# rfidboard.net
KiCad netlist of a schematic drawn in EAGLE
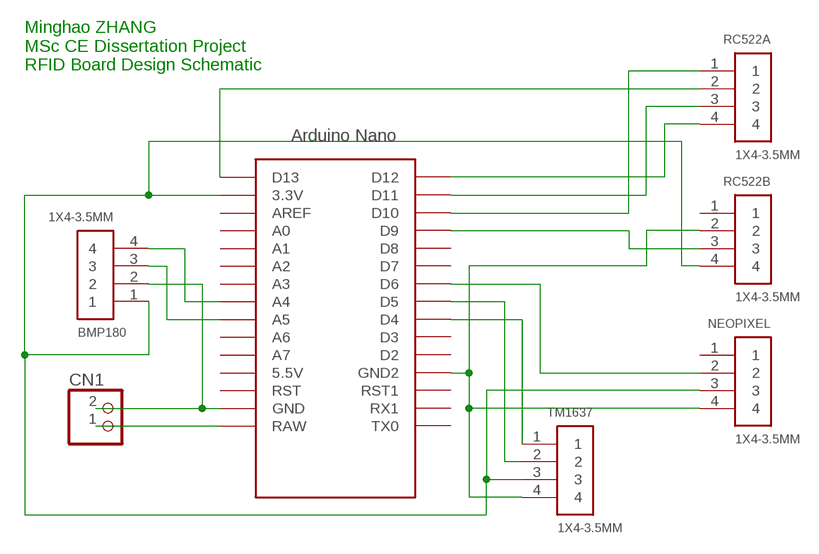
[diagram p0: schematic, sheet 1]

(export (version "E")
  (design (tool "Eeschema 10.0.6"))
  (components
    (comp (ref "BMP180")
      (value "1X4-3.5MM")
      (footprint "eagle-import:1X04-3.5MM")
      (libsource (lib "eagle-import") (part "1X4-3.5MM"))
    )
    (comp (ref "CN1")
      (value "JST_2PIN-SMT")
      (footprint "eagle-import:JST-PH-2-SMT")
      (libsource (lib "eagle-import") (part "JST_2PIN-SMT"))
    )
    (comp (ref "NEOPIXEL")
      (value "1X4-3.5MM")
      (footprint "eagle-import:1X04-3.5MM")
      (libsource (lib "eagle-import") (part "1X4-3.5MM"))
    )
    (comp (ref "RC522A")
      (value "1X4-3.5MM")
      (footprint "eagle-import:1X04-3.5MM")
      (libsource (lib "eagle-import") (part "1X4-3.5MM"))
    )
    (comp (ref "RC522B")
      (value "1X4-3.5MM")
      (footprint "eagle-import:1X04-3.5MM")
      (libsource (lib "eagle-import") (part "1X4-3.5MM"))
    )
    (comp (ref "TM1637")
      (value "1X4-3.5MM")
      (footprint "eagle-import:1X04-3.5MM")
      (libsource (lib "eagle-import") (part "1X4-3.5MM"))
    )
    (comp (ref "U$1")
      (value "NANO")
      (footprint "eagle-import:NANO")
      (libsource (lib "eagle-import") (part "NANO"))
    )
  )
  (nets
    (net (code "1") (name "Net-(BMP180-Pad1)") (class "Default")
      (node (ref "BMP180") (pin "1") (pinfunction "1_1") (pintype "bidirectional"))
      (node (ref "NEOPIXEL") (pin "3") (pinfunction "3_3") (pintype "bidirectional"))
      (node (ref "RC522B") (pin "4") (pinfunction "4_4") (pintype "bidirectional"))
      (node (ref "TM1637") (pin "3") (pinfunction "3_3") (pintype "bidirectional"))
      (node (ref "U$1") (pin "3.3V") (pinfunction "3.3V_3.3V") (pintype "bidirectional"))
    )
    (net (code "2") (name "Net-(BMP180-Pad3)") (class "Default")
      (node (ref "BMP180") (pin "3") (pinfunction "3_3") (pintype "bidirectional"))
      (node (ref "U$1") (pin "A5") (pinfunction "A5_A5") (pintype "bidirectional"))
    )
    (net (code "3") (name "Net-(BMP180-Pad4)") (class "Default")
      (node (ref "BMP180") (pin "4") (pinfunction "4_4") (pintype "bidirectional"))
      (node (ref "U$1") (pin "A4") (pinfunction "A4_A4") (pintype "bidirectional"))
    )
    (net (code "4") (name "Net-(CN1-1)") (class "Default")
      (node (ref "BMP180") (pin "2") (pinfunction "2_2") (pintype "bidirectional"))
      (node (ref "CN1") (pin "2") (pinfunction "1_2") (pintype "passive"))
      (node (ref "U$1") (pin "GND") (pinfunction "GND_GND") (pintype "bidirectional"))
    )
    (net (code "5") (name "Net-(CN1-2)") (class "Default")
      (node (ref "CN1") (pin "1") (pinfunction "2_1") (pintype "passive"))
      (node (ref "U$1") (pin "RAW") (pinfunction "RAW_RAW") (pintype "bidirectional"))
    )
    (net (code "6") (name "Net-(NEOPIXEL-Pad2)") (class "Default")
      (node (ref "NEOPIXEL") (pin "2") (pinfunction "2_2") (pintype "bidirectional"))
      (node (ref "U$1") (pin "D6") (pinfunction "D6_D6") (pintype "bidirectional"))
    )
    (net (code "7") (name "Net-(RC522A-Pad1)") (class "Default")
      (node (ref "RC522A") (pin "1") (pinfunction "1_1") (pintype "bidirectional"))
      (node (ref "U$1") (pin "D10") (pinfunction "D10_D10") (pintype "bidirectional"))
    )
    (net (code "8") (name "Net-(RC522A-Pad2)") (class "Default")
      (node (ref "RC522A") (pin "2") (pinfunction "2_2") (pintype "bidirectional"))
      (node (ref "U$1") (pin "D13") (pinfunction "D13_D13") (pintype "bidirectional"))
    )
    (net (code "9") (name "Net-(RC522A-Pad3)") (class "Default")
      (node (ref "RC522A") (pin "3") (pinfunction "3_3") (pintype "bidirectional"))
      (node (ref "U$1") (pin "D11") (pinfunction "D11_D11") (pintype "bidirectional"))
    )
    (net (code "10") (name "Net-(RC522A-Pad4)") (class "Default")
      (node (ref "RC522A") (pin "4") (pinfunction "4_4") (pintype "bidirectional"))
      (node (ref "U$1") (pin "D12") (pinfunction "D12_D12") (pintype "bidirectional"))
    )
    (net (code "11") (name "Net-(RC522B-Pad3)") (class "Default")
      (node (ref "RC522B") (pin "3") (pinfunction "3_3") (pintype "bidirectional"))
      (node (ref "U$1") (pin "D9") (pinfunction "D9_D9") (pintype "bidirectional"))
    )
    (net (code "12") (name "Net-(TM1637-Pad1)") (class "Default")
      (node (ref "TM1637") (pin "1") (pinfunction "1_1") (pintype "bidirectional"))
      (node (ref "U$1") (pin "D4") (pinfunction "D4_D4") (pintype "bidirectional"))
    )
    (net (code "13") (name "Net-(TM1637-Pad2)") (class "Default")
      (node (ref "TM1637") (pin "2") (pinfunction "2_2") (pintype "bidirectional"))
      (node (ref "U$1") (pin "D5") (pinfunction "D5_D5") (pintype "bidirectional"))
    )
    (net (code "14") (name "Net-(U$1-GND2)") (class "Default")
      (node (ref "NEOPIXEL") (pin "4") (pinfunction "4_4") (pintype "bidirectional"))
      (node (ref "RC522B") (pin "2") (pinfunction "2_2") (pintype "bidirectional"))
      (node (ref "TM1637") (pin "4") (pinfunction "4_4") (pintype "bidirectional"))
      (node (ref "U$1") (pin "GND1") (pinfunction "GND2_GND1") (pintype "bidirectional"))
    )
    (net (code "15") (name "unconnected-(NEOPIXEL-Pad1)") (class "Default")
      (node (ref "NEOPIXEL") (pin "1") (pinfunction "1_1") (pintype "bidirectional"))
    )
    (net (code "16") (name "unconnected-(RC522B-Pad1)") (class "Default")
      (node (ref "RC522B") (pin "1") (pinfunction "1_1") (pintype "bidirectional"))
    )
    (net (code "17") (name "unconnected-(U$1-5.5V-Pad5V)") (class "Default")
      (node (ref "U$1") (pin "5V") (pinfunction "5.5V_5V") (pintype "bidirectional"))
    )
    (net (code "18") (name "unconnected-(U$1-PadA0)") (class "Default")
      (node (ref "U$1") (pin "A0") (pinfunction "A0_A0") (pintype "bidirectional"))
    )
    (net (code "19") (name "unconnected-(U$1-PadA1)") (class "Default")
      (node (ref "U$1") (pin "A1") (pinfunction "A1_A1") (pintype "bidirectional"))
    )
    (net (code "20") (name "unconnected-(U$1-PadA2)") (class "Default")
      (node (ref "U$1") (pin "A2") (pinfunction "A2_A2") (pintype "bidirectional"))
    )
    (net (code "21") (name "unconnected-(U$1-PadA3)") (class "Default")
      (node (ref "U$1") (pin "A3") (pinfunction "A3_A3") (pintype "bidirectional"))
    )
    (net (code "22") (name "unconnected-(U$1-PadA6)") (class "Default")
      (node (ref "U$1") (pin "A6") (pinfunction "A6_A6") (pintype "bidirectional"))
    )
    (net (code "23") (name "unconnected-(U$1-PadA7)") (class "Default")
      (node (ref "U$1") (pin "A7") (pinfunction "A7_A7") (pintype "bidirectional"))
    )
    (net (code "24") (name "unconnected-(U$1-PadAREF)") (class "Default")
      (node (ref "U$1") (pin "AREF") (pinfunction "AREF_AREF") (pintype "bidirectional"))
    )
    (net (code "25") (name "unconnected-(U$1-PadD2)") (class "Default")
      (node (ref "U$1") (pin "D2") (pinfunction "D2_D2") (pintype "bidirectional"))
    )
    (net (code "26") (name "unconnected-(U$1-PadD3)") (class "Default")
      (node (ref "U$1") (pin "D3") (pinfunction "D3_D3") (pintype "bidirectional"))
    )
    (net (code "27") (name "unconnected-(U$1-PadD7)") (class "Default")
      (node (ref "U$1") (pin "D7") (pinfunction "D7_D7") (pintype "bidirectional"))
    )
    (net (code "28") (name "unconnected-(U$1-PadD8)") (class "Default")
      (node (ref "U$1") (pin "D8") (pinfunction "D8_D8") (pintype "bidirectional"))
    )
    (net (code "29") (name "unconnected-(U$1-PadICSP1)") (class "Default")
      (node (ref "U$1") (pin "ICSP1") (pinfunction "ICSP1_ICSP1") (pintype "bidirectional"))
    )
    (net (code "30") (name "unconnected-(U$1-PadICSP2)") (class "Default")
      (node (ref "U$1") (pin "ICSP2") (pinfunction "ICSP2_ICSP2") (pintype "bidirectional"))
    )
    (net (code "31") (name "unconnected-(U$1-PadICSP3)") (class "Default")
      (node (ref "U$1") (pin "ICSP3") (pinfunction "ICSP3_ICSP3") (pintype "bidirectional"))
    )
    (net (code "32") (name "unconnected-(U$1-PadICSP4)") (class "Default")
      (node (ref "U$1") (pin "ICSP4") (pinfunction "ICSP4_ICSP4") (pintype "bidirectional"))
    )
    (net (code "33") (name "unconnected-(U$1-PadICSP5)") (class "Default")
      (node (ref "U$1") (pin "ICSP5") (pinfunction "ICSP5_ICSP5") (pintype "bidirectional"))
    )
    (net (code "34") (name "unconnected-(U$1-PadICSP6)") (class "Default")
      (node (ref "U$1") (pin "ICSP6") (pinfunction "ICSP6_ICSP6") (pintype "bidirectional"))
    )
    (net (code "35") (name "unconnected-(U$1-PadRST)") (class "Default")
      (node (ref "U$1") (pin "RST") (pinfunction "RST_RST") (pintype "bidirectional"))
    )
    (net (code "36") (name "unconnected-(U$1-PadRST1)") (class "Default")
      (node (ref "U$1") (pin "RST1") (pinfunction "RST1_RST1") (pintype "bidirectional"))
    )
    (net (code "37") (name "unconnected-(U$1-PadRX1)") (class "Default")
      (node (ref "U$1") (pin "RX1") (pinfunction "RX1_RX1") (pintype "bidirectional"))
    )
    (net (code "38") (name "unconnected-(U$1-PadTX0)") (class "Default")
      (node (ref "U$1") (pin "TX0") (pinfunction "TX0_TX0") (pintype "bidirectional"))
    )
  )
)
